# OM-02P.net
KiCad netlist of a schematic drawn in Altium Designer
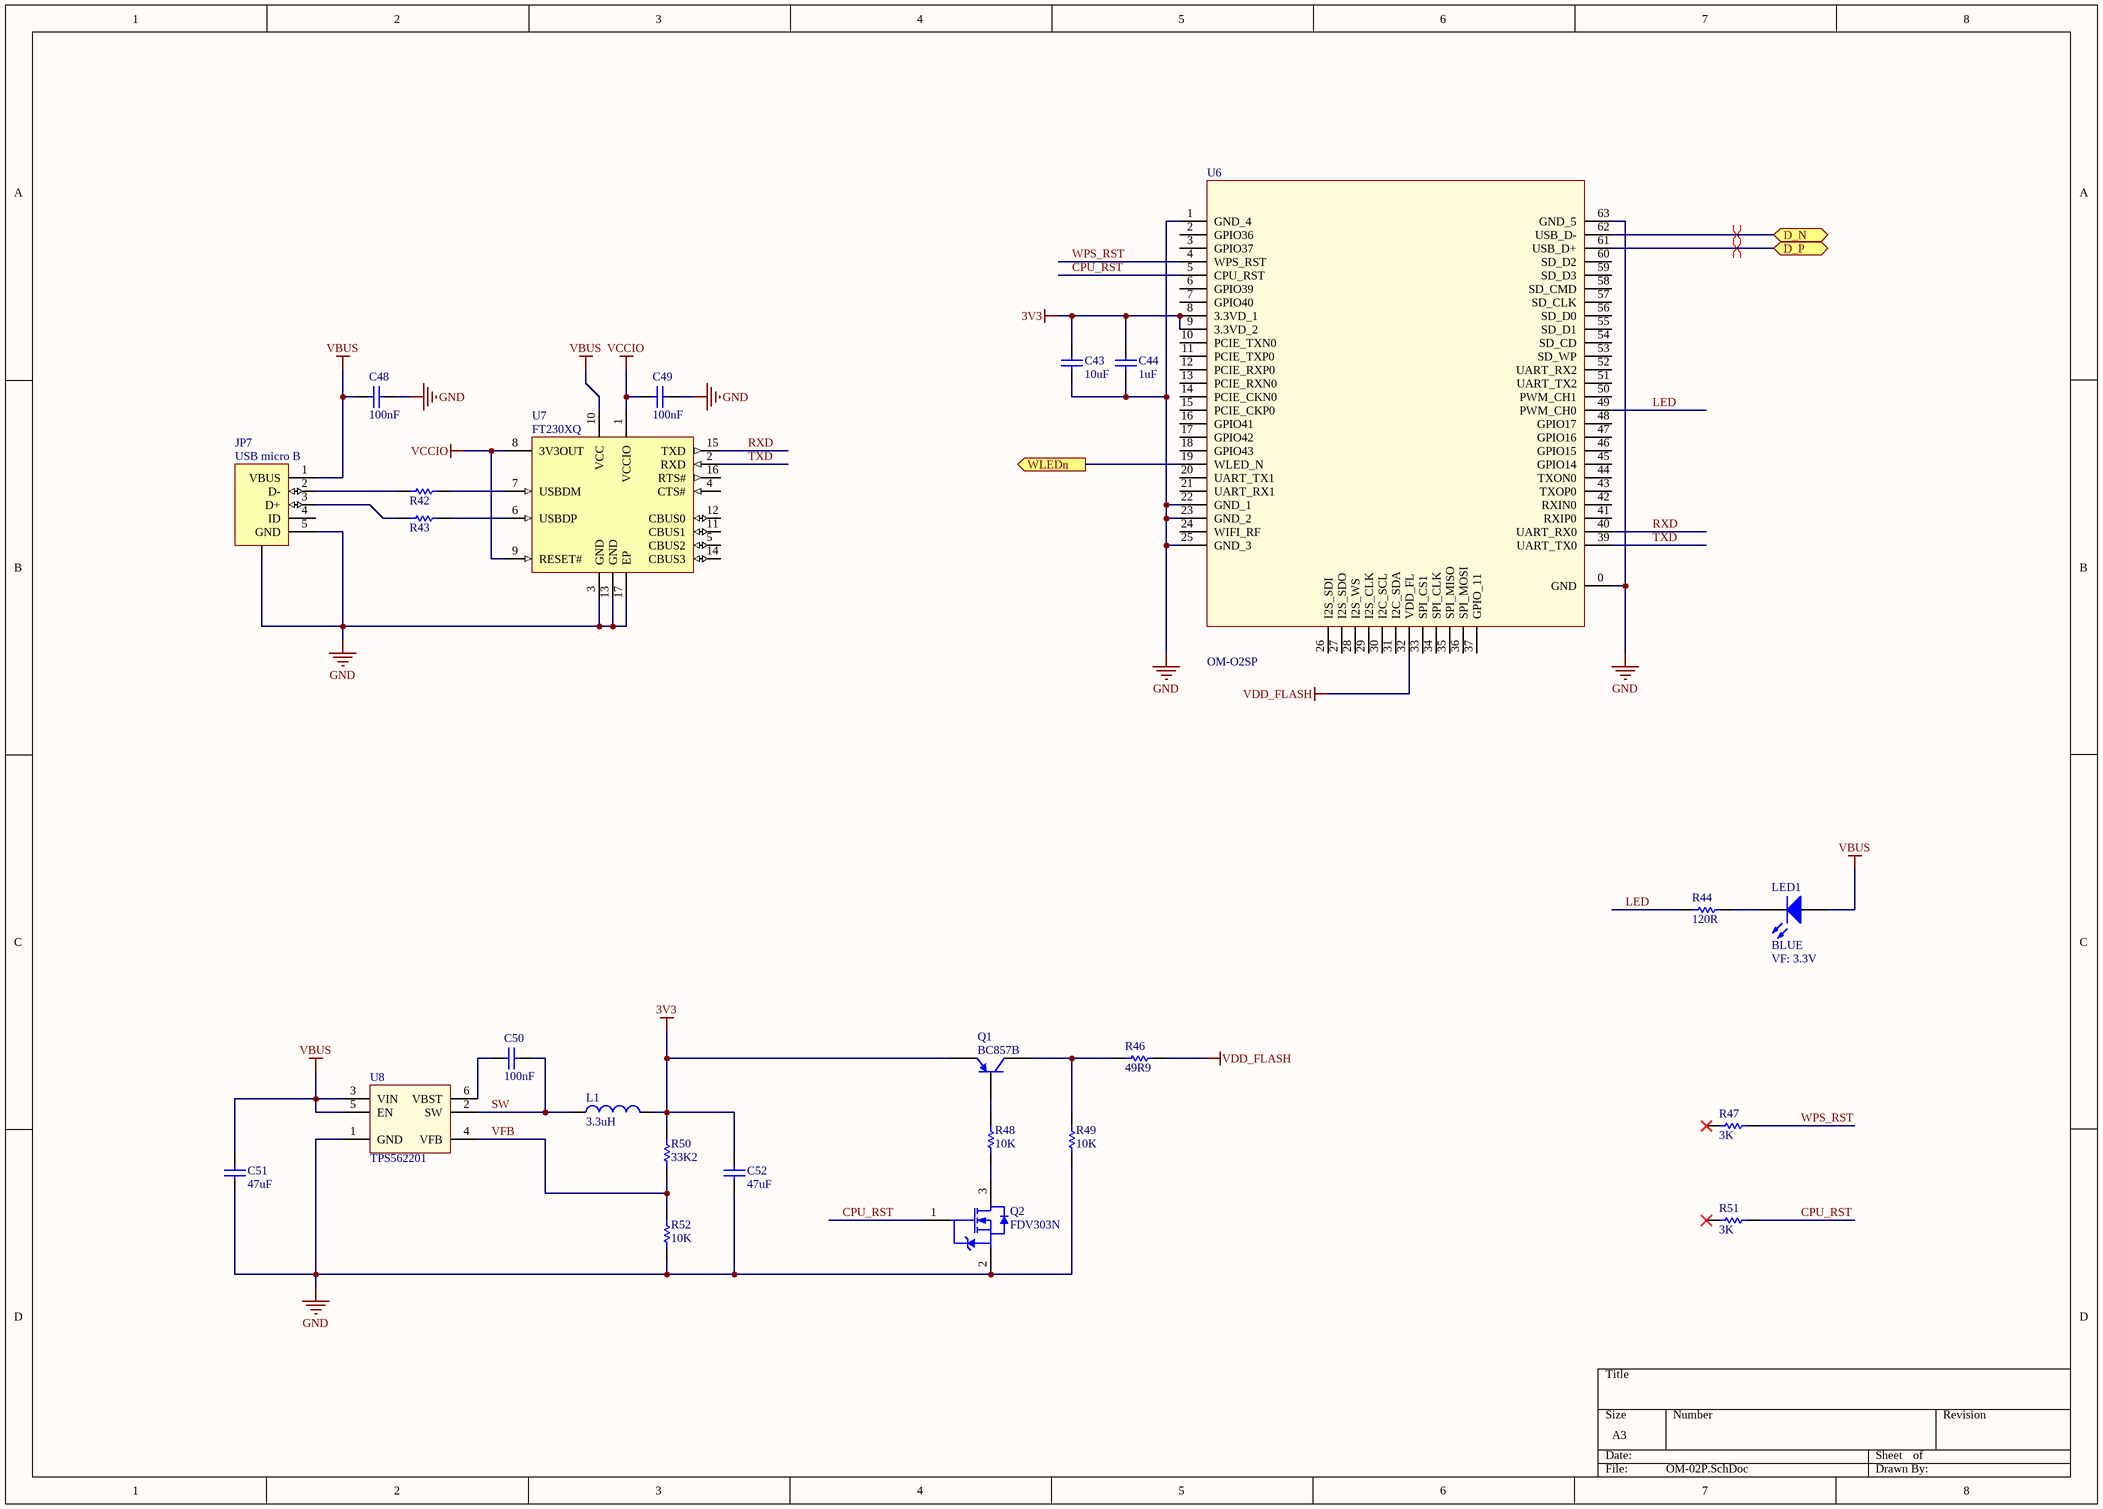
[diagram p0: OM-02P.SchDoc]

(export (version "E")
  (design (tool "Eeschema 10.0.6"))
  (components
    (comp (ref "C43")
      (value "10uF")
      (footprint "CAPC0805(2012)145_N")
      (description "CAP 10uF 16V ±20% 0805 (2012 Metric) Thickness 1.45mm SMD")
      (fields (field (name "TOLERANCE") "Â±20%") (field (name "Comment") "CAP 10uF 16V 0805(2012)"))
      (libsource (lib "Altium Content Vault") (part "CMP-1036-04929-1"))
    )
    (comp (ref "C44")
      (value "1uF")
      (footprint "CAPC0805(2012)145_N")
      (description "CAP 1uF 16V ±20% 0805 (2012 Metric) Thickness 1.45mm SMD")
      (fields (field (name "TOLERANCE") "Â±20%") (field (name "Comment") "CAP 1uF 16V 0805(2012)"))
      (libsource (lib "Altium Content Vault") (part "CMP-1036-04748-1"))
    )
    (comp (ref "C48")
      (value "100nF")
      (footprint "CAPC0805(2012)100_M")
      (description "CAP 100nF 16V ±5% 0805 (2012 Metric) Thickness 1mm SMD")
      (fields (field (name "TOLERANCE") "Â±5%") (field (name "Comment") "CAP 100nF 16V 0805(2012)"))
      (libsource (lib "Altium Content Vault") (part "CAP"))
    )
    (comp (ref "C49")
      (value "100nF")
      (footprint "CAPC0805(2012)100_M")
      (description "CAP 100nF 16V ±5% 0805 (2012 Metric) Thickness 1mm SMD")
      (fields (field (name "TOLERANCE") "Â±5%") (field (name "Comment") "CAP 100nF 16V 0805(2012)"))
      (libsource (lib "Altium Content Vault") (part "CAP"))
    )
    (comp (ref "C50")
      (value "100nF")
      (footprint "CAPC0805(2012)100_N")
      (description "CAP 100nF 16V ±5% 0805 (2012 Metric) Thickness 1mm SMD")
      (fields (field (name "TOLERANCE") "Â±5%") (field (name "Comment") "CAP 100nF 16V 0805(2012)"))
      (libsource (lib "Altium Content Vault") (part "CAP"))
    )
    (comp (ref "C51")
      (value "47uF")
      (footprint "CAPC1210(3225)280_N")
      (description "CAP 47uF 16V ±20% 1210 (3225 Metric) Thickness 2.8mm SMD")
      (fields (field (name "TOLERANCE") "Â±20%") (field (name "MPN") "C1210C476M4PACTU"))
      (libsource (lib "Altium Content Vault") (part "CAP"))
    )
    (comp (ref "C52")
      (value "47uF")
      (footprint "CAPC1210(3225)280_N")
      (description "CAP 47uF 16V ±20% 1210 (3225 Metric) Thickness 2.8mm SMD")
      (fields (field (name "TOLERANCE") "Â±20%") (field (name "MPN") "C1210C476M4PACTU"))
      (libsource (lib "Altium Content Vault") (part "CAP"))
    )
    (comp (ref "JP7")
      (value "USB micro B")
      (footprint "CONN_USB_MICRO_B_105017")
      (description "USB - micro B USB 2.0 Receptacle Connector 5 Position Surface Mount, Right Angle")
      (fields (field (name "MPN") "1050170001"))
      (libsource (lib "micun") (part "CONN_USB_MICRO_B_105017"))
    )
    (comp (ref "L1")
      (value "3.3uH")
      (footprint "CAPC1008(2520)")
      (description "3.3µH Shielded Wirewound Inductor 1.7A 156 mOhm Max 1008 (2520 Metric)")
      (fields (field (name "MPN") "MAMK2520T3R3M"))
      (libsource (lib "micun") (part "L-MAMK2520T3R3M"))
    )
    (comp (ref "LED1")
      (value "BLUE")
      (footprint "LED-KA-4040QBS-D")
      (description "LED 0805")
      (fields (field (name "MPN") "KA-4040QBS-D") (field (name "VF") "3.3V"))
      (libsource (lib "micun") (part "LED-BLUE-KA-4040QBS-D"))
    )
    (comp (ref "Q1")
      (value "BC857B")
      (footprint "INF-SOT23_M")
      (description "PNP Silicon AF Transistor, 45 V VCEO, 100 mA IC, SOT23, Reel, Green")
      (fields (field (name "MANUFACTURER") "Infineon"))
      (libsource (lib "Altium Content Vault") (part "INF-BJTPNP-BEC-3"))
    )
    (comp (ref "Q2")
      (value "FDV303N")
      (footprint "FAIR-FDV303N-3_V")
      (fields (field (name "MANUFACTURER") "Fairchild"))
      (libsource (lib "Altium Content Vault") (part "NEMOS-GSD-3_D"))
    )
    (comp (ref "R42")
      (value "RES")
      (footprint "RESC0402(1005)_L")
      (description "Generic resistor")
      (libsource (lib "micun") (part "RES"))
    )
    (comp (ref "R43")
      (value "RES")
      (footprint "RESC0402(1005)_L")
      (description "Generic resistor")
      (libsource (lib "micun") (part "RES"))
    )
    (comp (ref "R44")
      (value "120R")
      (footprint "RESC0805(2012)_N")
      (description "120R 0.125W 5% 0805 (2012 Metric)  SMD")
      (fields (field (name "TOLERANCE") "5 %") (field (name "POWER") "0.125 W"))
      (libsource (lib "Altium Content Vault") (part "RES"))
    )
    (comp (ref "R46")
      (value "49R9")
      (footprint "RESC0805(2012)_N")
      (description "49R9 0.125W 1% 0805 (2012 Metric)  SMD")
      (fields (field (name "POWER") "0.125 W") (field (name "TOLERANCE") "1 %"))
      (libsource (lib "Altium Content Vault") (part "RES"))
    )
    (comp (ref "R47")
      (value "3K")
      (footprint "RESC0805(2012)_M")
      (description "3K 0.125W 5% 0805 (2012 Metric)  SMD")
      (fields (field (name "POWER") "0.125 W") (field (name "TOLERANCE") "5 %"))
      (libsource (lib "Altium Content Vault") (part "RES"))
    )
    (comp (ref "R48")
      (value "10K")
      (footprint "RESC0805(2012)_N")
      (description "10K 0.125W 5% 0805 (2012 Metric)  SMD")
      (fields (field (name "POWER") "0.125 W") (field (name "TOLERANCE") "5 %"))
      (libsource (lib "Altium Content Vault") (part "RES"))
    )
    (comp (ref "R49")
      (value "10K")
      (footprint "RESC0805(2012)_N")
      (description "10K 0.125W 5% 0805 (2012 Metric)  SMD")
      (fields (field (name "POWER") "0.125 W") (field (name "TOLERANCE") "5 %"))
      (libsource (lib "Altium Content Vault") (part "RES"))
    )
    (comp (ref "R50")
      (value "33K2")
      (footprint "RESC0805(2012)_N")
      (description "33K2 0.125W 1% 0805 (2012 Metric)  SMD")
      (fields (field (name "TOLERANCE") "1 %") (field (name "POWER") "0.125 W"))
      (libsource (lib "Altium Content Vault") (part "RES"))
    )
    (comp (ref "R51")
      (value "3K")
      (footprint "RESC0805(2012)_M")
      (description "3K 0.125W 5% 0805 (2012 Metric)  SMD")
      (fields (field (name "POWER") "0.125 W") (field (name "TOLERANCE") "5 %"))
      (libsource (lib "Altium Content Vault") (part "RES"))
    )
    (comp (ref "R52")
      (value "10K")
      (footprint "RESC0805(2012)_N")
      (description "10K 0.125W 1% 0805 (2012 Metric)  SMD")
      (fields (field (name "TOLERANCE") "1 %") (field (name "POWER") "0.125 W"))
      (libsource (lib "Altium Content Vault") (part "RES"))
    )
    (comp (ref "U6")
      (value "OM-O2SP")
      (footprint "CPU-OM-O2S")
      (description "Onion Omega2S")
      (libsource (lib "micun") (part "CPU-OM-O2SP"))
    )
    (comp (ref "U7")
      (value "FT230XQ")
      (footprint "QFN-16_N")
      (libsource (lib "micun") (part "IC-COM-USB-FT230XQ-SQ17"))
    )
    (comp (ref "U8")
      (value "TPS562201")
      (footprint "SOT23-6_L")
      (description "Buck Switching Regulator IC Positive Adjustable 0.768V 1 Output 2A SOT-23-6 Thin, TSOT-23-6")
      (fields (field (name "MPN") "TPS562201DDCT"))
      (libsource (lib "micun") (part "IC-PMIC-TPS562201"))
    )
  )
  (nets
    (net (code "1") (name "/CPU_RST") (class "Default")
      (node (ref "Q2") (pin "1") (pinfunction "G_1") (pintype "passive"))
      (node (ref "R51") (pin "1") (pinfunction "1_1") (pintype "passive"))
      (node (ref "U6") (pin "5") (pinfunction "CPU_RST_5") (pintype "passive"))
    )
    (net (code "2") (name "/D_N") (class "Default")
      (node (ref "U6") (pin "62") (pinfunction "USB_D-_62") (pintype "passive"))
    )
    (net (code "3") (name "/D_P") (class "Default")
      (node (ref "U6") (pin "61") (pinfunction "USB_D+_61") (pintype "passive"))
    )
    (net (code "4") (name "/LED") (class "Default")
      (node (ref "R44") (pin "2") (pinfunction "2_2") (pintype "passive"))
      (node (ref "U6") (pin "49") (pinfunction "PWM_CH0_49") (pintype "passive"))
    )
    (net (code "5") (name "/RXD") (class "Default")
      (node (ref "U6") (pin "40") (pinfunction "UART_RX0_40") (pintype "passive"))
      (node (ref "U7") (pin "15") (pinfunction "TXD_15") (pintype "output"))
    )
    (net (code "6") (name "/SW") (class "Default")
      (node (ref "C50") (pin "1") (pinfunction "1_1") (pintype "passive"))
      (node (ref "L1") (pin "1") (pinfunction "1_1") (pintype "passive"))
      (node (ref "U8") (pin "2") (pinfunction "SW_2") (pintype "passive"))
    )
    (net (code "7") (name "/TXD") (class "Default")
      (node (ref "U6") (pin "39") (pinfunction "UART_TX0_39") (pintype "passive"))
      (node (ref "U7") (pin "2") (pinfunction "RXD_2") (pintype "input"))
    )
    (net (code "8") (name "/VFB") (class "Default")
      (node (ref "R50") (pin "1") (pinfunction "1_1") (pintype "passive"))
      (node (ref "R52") (pin "2") (pinfunction "2_2") (pintype "passive"))
      (node (ref "U8") (pin "4") (pinfunction "VFB_4") (pintype "passive"))
    )
    (net (code "9") (name "/WLEDn") (class "Default")
      (node (ref "U6") (pin "19") (pinfunction "WLED_N_19") (pintype "passive"))
    )
    (net (code "10") (name "/WPS_RST") (class "Default")
      (node (ref "R47") (pin "1") (pinfunction "1_1") (pintype "passive"))
      (node (ref "U6") (pin "4") (pinfunction "WPS_RST_4") (pintype "passive"))
    )
    (net (code "11") (name "3V3") (class "Default")
      (node (ref "C43") (pin "2") (pinfunction "2_2") (pintype "passive"))
      (node (ref "C44") (pin "2") (pinfunction "2_2") (pintype "passive"))
      (node (ref "C52") (pin "2") (pinfunction "2_2") (pintype "passive"))
      (node (ref "L1") (pin "2") (pinfunction "2_2") (pintype "passive"))
      (node (ref "Q1") (pin "2") (pinfunction "E_2") (pintype "passive"))
      (node (ref "R50") (pin "2") (pinfunction "2_2") (pintype "passive"))
      (node (ref "U6") (pin "8") (pinfunction "3.3VD_1_8") (pintype "power_in"))
      (node (ref "U6") (pin "9") (pinfunction "3.3VD_2_9") (pintype "power_in"))
    )
    (net (code "12") (name "GND") (class "Default")
      (node (ref "C43") (pin "1") (pinfunction "1_1") (pintype "passive"))
      (node (ref "C44") (pin "1") (pinfunction "1_1") (pintype "passive"))
      (node (ref "C48") (pin "1") (pinfunction "1_1") (pintype "passive"))
      (node (ref "C49") (pin "1") (pinfunction "1_1") (pintype "passive"))
      (node (ref "C51") (pin "1") (pinfunction "1_1") (pintype "passive"))
      (node (ref "C52") (pin "1") (pinfunction "1_1") (pintype "passive"))
      (node (ref "JP7") (pin "0") (pinfunction "CHS_0") (pintype "passive"))
      (node (ref "JP7") (pin "5") (pinfunction "GND_5") (pintype "power_in"))
      (node (ref "Q2") (pin "2") (pinfunction "S_2") (pintype "passive"))
      (node (ref "R49") (pin "2") (pinfunction "2_2") (pintype "passive"))
      (node (ref "R52") (pin "1") (pinfunction "1_1") (pintype "passive"))
      (node (ref "U6") (pin "0") (pinfunction "GND_0") (pintype "passive"))
      (node (ref "U6") (pin "1") (pinfunction "GND_4_1") (pintype "power_in"))
      (node (ref "U6") (pin "22") (pinfunction "GND_1_22") (pintype "power_in"))
      (node (ref "U6") (pin "23") (pinfunction "GND_2_23") (pintype "power_in"))
      (node (ref "U6") (pin "25") (pinfunction "GND_3_25") (pintype "power_in"))
      (node (ref "U6") (pin "63") (pinfunction "GND_5_63") (pintype "power_in"))
      (node (ref "U7") (pin "13") (pinfunction "GND_13") (pintype "power_in"))
      (node (ref "U7") (pin "17") (pinfunction "EP_17") (pintype "power_in"))
      (node (ref "U7") (pin "3") (pinfunction "GND_3") (pintype "power_in"))
      (node (ref "U8") (pin "1") (pinfunction "GND_1") (pintype "power_in"))
    )
    (net (code "13") (name "Net-(JP7-D+)") (class "Default")
      (node (ref "JP7") (pin "3") (pinfunction "D+_3") (pintype "bidirectional"))
      (node (ref "R43") (pin "1") (pinfunction "1_1") (pintype "passive"))
    )
    (net (code "14") (name "Net-(JP7-D-)") (class "Default")
      (node (ref "JP7") (pin "2") (pinfunction "D-_2") (pintype "bidirectional"))
      (node (ref "R42") (pin "1") (pinfunction "1_1") (pintype "passive"))
    )
    (net (code "15") (name "Net-(LED1-PadK)") (class "Default")
      (node (ref "LED1") (pin "K") (pinfunction "K_K") (pintype "passive"))
      (node (ref "R44") (pin "1") (pinfunction "1_1") (pintype "passive"))
    )
    (net (code "16") (name "Net-(Q1-B)") (class "Default")
      (node (ref "Q1") (pin "1") (pinfunction "B_1") (pintype "passive"))
      (node (ref "R48") (pin "1") (pinfunction "1_1") (pintype "passive"))
    )
    (net (code "17") (name "Net-(Q1-C)") (class "Default")
      (node (ref "Q1") (pin "3") (pinfunction "C_3") (pintype "passive"))
      (node (ref "R46") (pin "1") (pinfunction "1_1") (pintype "passive"))
      (node (ref "R49") (pin "1") (pinfunction "1_1") (pintype "passive"))
    )
    (net (code "18") (name "Net-(Q2-D)") (class "Default")
      (node (ref "Q2") (pin "3") (pinfunction "D_3") (pintype "passive"))
      (node (ref "R48") (pin "2") (pinfunction "2_2") (pintype "passive"))
    )
    (net (code "19") (name "Net-(U7-USBDM)") (class "Default")
      (node (ref "R42") (pin "2") (pinfunction "2_2") (pintype "passive"))
      (node (ref "U7") (pin "7") (pinfunction "USBDM_7") (pintype "input"))
    )
    (net (code "20") (name "Net-(U7-USBDP)") (class "Default")
      (node (ref "R43") (pin "2") (pinfunction "2_2") (pintype "passive"))
      (node (ref "U7") (pin "6") (pinfunction "USBDP_6") (pintype "input"))
    )
    (net (code "21") (name "Net-(U8-VBST)") (class "Default")
      (node (ref "C50") (pin "2") (pinfunction "2_2") (pintype "passive"))
      (node (ref "U8") (pin "6") (pinfunction "VBST_6") (pintype "power_in"))
    )
    (net (code "22") (name "VBUS") (class "Default")
      (node (ref "C48") (pin "2") (pinfunction "2_2") (pintype "passive"))
      (node (ref "C51") (pin "2") (pinfunction "2_2") (pintype "passive"))
      (node (ref "JP7") (pin "1") (pinfunction "VBUS_1") (pintype "power_in"))
      (node (ref "LED1") (pin "A") (pinfunction "A_A") (pintype "passive"))
      (node (ref "U7") (pin "10") (pinfunction "VCC_10") (pintype "power_in"))
      (node (ref "U8") (pin "3") (pinfunction "VIN_3") (pintype "power_in"))
      (node (ref "U8") (pin "5") (pinfunction "EN_5") (pintype "passive"))
    )
    (net (code "23") (name "VCCIO") (class "Default")
      (node (ref "C49") (pin "2") (pinfunction "2_2") (pintype "passive"))
      (node (ref "U7") (pin "1") (pinfunction "VCCIO_1") (pintype "power_in"))
      (node (ref "U7") (pin "8") (pinfunction "3V3OUT_8") (pintype "power_in"))
      (node (ref "U7") (pin "9") (pinfunction "RESET#_9") (pintype "input"))
    )
    (net (code "24") (name "VDD_FLASH") (class "Default")
      (node (ref "R46") (pin "2") (pinfunction "2_2") (pintype "passive"))
      (node (ref "U6") (pin "32") (pinfunction "VDD_FL_32") (pintype "power_in"))
    )
    (net (code "25") (name "unconnected-(JP7-ID-Pad4)") (class "Default")
      (node (ref "JP7") (pin "4") (pinfunction "ID_4") (pintype "passive"))
    )
    (net (code "26") (name "unconnected-(R47-Pad2)") (class "Default")
      (node (ref "R47") (pin "2") (pinfunction "2_2") (pintype "passive+no_connect"))
    )
    (net (code "27") (name "unconnected-(R51-Pad2)") (class "Default")
      (node (ref "R51") (pin "2") (pinfunction "2_2") (pintype "passive+no_connect"))
    )
    (net (code "28") (name "unconnected-(U6-GPIO14-Pad45)") (class "Default")
      (node (ref "U6") (pin "45") (pinfunction "GPIO14_45") (pintype "passive"))
    )
    (net (code "29") (name "unconnected-(U6-GPIO15-Pad46)") (class "Default")
      (node (ref "U6") (pin "46") (pinfunction "GPIO15_46") (pintype "passive"))
    )
    (net (code "30") (name "unconnected-(U6-GPIO16-Pad47)") (class "Default")
      (node (ref "U6") (pin "47") (pinfunction "GPIO16_47") (pintype "passive"))
    )
    (net (code "31") (name "unconnected-(U6-GPIO17-Pad48)") (class "Default")
      (node (ref "U6") (pin "48") (pinfunction "GPIO17_48") (pintype "passive"))
    )
    (net (code "32") (name "unconnected-(U6-GPIO36-Pad2)") (class "Default")
      (node (ref "U6") (pin "2") (pinfunction "GPIO36_2") (pintype "passive"))
    )
    (net (code "33") (name "unconnected-(U6-GPIO37-Pad3)") (class "Default")
      (node (ref "U6") (pin "3") (pinfunction "GPIO37_3") (pintype "passive"))
    )
    (net (code "34") (name "unconnected-(U6-GPIO39-Pad6)") (class "Default")
      (node (ref "U6") (pin "6") (pinfunction "GPIO39_6") (pintype "passive"))
    )
    (net (code "35") (name "unconnected-(U6-GPIO40-Pad7)") (class "Default")
      (node (ref "U6") (pin "7") (pinfunction "GPIO40_7") (pintype "passive"))
    )
    (net (code "36") (name "unconnected-(U6-GPIO41-Pad16)") (class "Default")
      (node (ref "U6") (pin "16") (pinfunction "GPIO41_16") (pintype "passive"))
    )
    (net (code "37") (name "unconnected-(U6-GPIO42-Pad17)") (class "Default")
      (node (ref "U6") (pin "17") (pinfunction "GPIO42_17") (pintype "passive"))
    )
    (net (code "38") (name "unconnected-(U6-GPIO43-Pad18)") (class "Default")
      (node (ref "U6") (pin "18") (pinfunction "GPIO43_18") (pintype "passive"))
    )
    (net (code "39") (name "unconnected-(U6-GPIO_11-Pad37)") (class "Default")
      (node (ref "U6") (pin "37") (pinfunction "GPIO_11_37") (pintype "passive"))
    )
    (net (code "40") (name "unconnected-(U6-I2C_SCL-Pad30)") (class "Default")
      (node (ref "U6") (pin "30") (pinfunction "I2C_SCL_30") (pintype "passive"))
    )
    (net (code "41") (name "unconnected-(U6-I2C_SDA-Pad31)") (class "Default")
      (node (ref "U6") (pin "31") (pinfunction "I2C_SDA_31") (pintype "passive"))
    )
    (net (code "42") (name "unconnected-(U6-I2S_CLK-Pad29)") (class "Default")
      (node (ref "U6") (pin "29") (pinfunction "I2S_CLK_29") (pintype "passive"))
    )
    (net (code "43") (name "unconnected-(U6-I2S_SDI-Pad26)") (class "Default")
      (node (ref "U6") (pin "26") (pinfunction "I2S_SDI_26") (pintype "passive"))
    )
    (net (code "44") (name "unconnected-(U6-I2S_SDO-Pad27)") (class "Default")
      (node (ref "U6") (pin "27") (pinfunction "I2S_SDO_27") (pintype "passive"))
    )
    (net (code "45") (name "unconnected-(U6-I2S_WS-Pad28)") (class "Default")
      (node (ref "U6") (pin "28") (pinfunction "I2S_WS_28") (pintype "passive"))
    )
    (net (code "46") (name "unconnected-(U6-PCIE_CKN0-Pad14)") (class "Default")
      (node (ref "U6") (pin "14") (pinfunction "PCIE_CKN0_14") (pintype "passive"))
    )
    (net (code "47") (name "unconnected-(U6-PCIE_CKP0-Pad15)") (class "Default")
      (node (ref "U6") (pin "15") (pinfunction "PCIE_CKP0_15") (pintype "passive"))
    )
    (net (code "48") (name "unconnected-(U6-PCIE_RXN0-Pad13)") (class "Default")
      (node (ref "U6") (pin "13") (pinfunction "PCIE_RXN0_13") (pintype "passive"))
    )
    (net (code "49") (name "unconnected-(U6-PCIE_RXP0-Pad12)") (class "Default")
      (node (ref "U6") (pin "12") (pinfunction "PCIE_RXP0_12") (pintype "passive"))
    )
    (net (code "50") (name "unconnected-(U6-PCIE_TXN0-Pad10)") (class "Default")
      (node (ref "U6") (pin "10") (pinfunction "PCIE_TXN0_10") (pintype "passive"))
    )
    (net (code "51") (name "unconnected-(U6-PCIE_TXP0-Pad11)") (class "Default")
      (node (ref "U6") (pin "11") (pinfunction "PCIE_TXP0_11") (pintype "passive"))
    )
    (net (code "52") (name "unconnected-(U6-PWM_CH1-Pad50)") (class "Default")
      (node (ref "U6") (pin "50") (pinfunction "PWM_CH1_50") (pintype "passive"))
    )
    (net (code "53") (name "unconnected-(U6-RXIN0-Pad42)") (class "Default")
      (node (ref "U6") (pin "42") (pinfunction "RXIN0_42") (pintype "passive"))
    )
    (net (code "54") (name "unconnected-(U6-RXIP0-Pad41)") (class "Default")
      (node (ref "U6") (pin "41") (pinfunction "RXIP0_41") (pintype "passive"))
    )
    (net (code "55") (name "unconnected-(U6-SD_CD-Pad54)") (class "Default")
      (node (ref "U6") (pin "54") (pinfunction "SD_CD_54") (pintype "passive"))
    )
    (net (code "56") (name "unconnected-(U6-SD_CLK-Pad57)") (class "Default")
      (node (ref "U6") (pin "57") (pinfunction "SD_CLK_57") (pintype "passive"))
    )
    (net (code "57") (name "unconnected-(U6-SD_CMD-Pad58)") (class "Default")
      (node (ref "U6") (pin "58") (pinfunction "SD_CMD_58") (pintype "passive"))
    )
    (net (code "58") (name "unconnected-(U6-SD_D0-Pad56)") (class "Default")
      (node (ref "U6") (pin "56") (pinfunction "SD_D0_56") (pintype "passive"))
    )
    (net (code "59") (name "unconnected-(U6-SD_D1-Pad55)") (class "Default")
      (node (ref "U6") (pin "55") (pinfunction "SD_D1_55") (pintype "passive"))
    )
    (net (code "60") (name "unconnected-(U6-SD_D2-Pad60)") (class "Default")
      (node (ref "U6") (pin "60") (pinfunction "SD_D2_60") (pintype "passive"))
    )
    (net (code "61") (name "unconnected-(U6-SD_D3-Pad59)") (class "Default")
      (node (ref "U6") (pin "59") (pinfunction "SD_D3_59") (pintype "passive"))
    )
    (net (code "62") (name "unconnected-(U6-SD_WP-Pad53)") (class "Default")
      (node (ref "U6") (pin "53") (pinfunction "SD_WP_53") (pintype "passive"))
    )
    (net (code "63") (name "unconnected-(U6-SPI_CLK-Pad34)") (class "Default")
      (node (ref "U6") (pin "34") (pinfunction "SPI_CLK_34") (pintype "passive"))
    )
    (net (code "64") (name "unconnected-(U6-SPI_CS1-Pad33)") (class "Default")
      (node (ref "U6") (pin "33") (pinfunction "SPI_CS1_33") (pintype "passive"))
    )
    (net (code "65") (name "unconnected-(U6-SPI_MISO-Pad35)") (class "Default")
      (node (ref "U6") (pin "35") (pinfunction "SPI_MISO_35") (pintype "passive"))
    )
    (net (code "66") (name "unconnected-(U6-SPI_MOSI-Pad36)") (class "Default")
      (node (ref "U6") (pin "36") (pinfunction "SPI_MOSI_36") (pintype "passive"))
    )
    (net (code "67") (name "unconnected-(U6-TXON0-Pad44)") (class "Default")
      (node (ref "U6") (pin "44") (pinfunction "TXON0_44") (pintype "passive"))
    )
    (net (code "68") (name "unconnected-(U6-TXOP0-Pad43)") (class "Default")
      (node (ref "U6") (pin "43") (pinfunction "TXOP0_43") (pintype "passive"))
    )
    (net (code "69") (name "unconnected-(U6-UART_RX1-Pad21)") (class "Default")
      (node (ref "U6") (pin "21") (pinfunction "UART_RX1_21") (pintype "passive"))
    )
    (net (code "70") (name "unconnected-(U6-UART_RX2-Pad52)") (class "Default")
      (node (ref "U6") (pin "52") (pinfunction "UART_RX2_52") (pintype "passive"))
    )
    (net (code "71") (name "unconnected-(U6-UART_TX1-Pad20)") (class "Default")
      (node (ref "U6") (pin "20") (pinfunction "UART_TX1_20") (pintype "passive"))
    )
    (net (code "72") (name "unconnected-(U6-UART_TX2-Pad51)") (class "Default")
      (node (ref "U6") (pin "51") (pinfunction "UART_TX2_51") (pintype "passive"))
    )
    (net (code "73") (name "unconnected-(U6-WIFI_RF-Pad24)") (class "Default")
      (node (ref "U6") (pin "24") (pinfunction "WIFI_RF_24") (pintype "passive"))
    )
    (net (code "74") (name "unconnected-(U7-CBUS0-Pad12)") (class "Default")
      (node (ref "U7") (pin "12") (pinfunction "CBUS0_12") (pintype "bidirectional"))
    )
    (net (code "75") (name "unconnected-(U7-CBUS1-Pad11)") (class "Default")
      (node (ref "U7") (pin "11") (pinfunction "CBUS1_11") (pintype "bidirectional"))
    )
    (net (code "76") (name "unconnected-(U7-CBUS2-Pad5)") (class "Default")
      (node (ref "U7") (pin "5") (pinfunction "CBUS2_5") (pintype "bidirectional"))
    )
    (net (code "77") (name "unconnected-(U7-CBUS3-Pad14)") (class "Default")
      (node (ref "U7") (pin "14") (pinfunction "CBUS3_14") (pintype "bidirectional"))
    )
    (net (code "78") (name "unconnected-(U7-CTS#-Pad4)") (class "Default")
      (node (ref "U7") (pin "4") (pinfunction "CTS#_4") (pintype "input"))
    )
    (net (code "79") (name "unconnected-(U7-RTS#-Pad16)") (class "Default")
      (node (ref "U7") (pin "16") (pinfunction "RTS#_16") (pintype "output"))
    )
  )
)
